# led.net
KiCad netlist of a schematic drawn in EAGLE
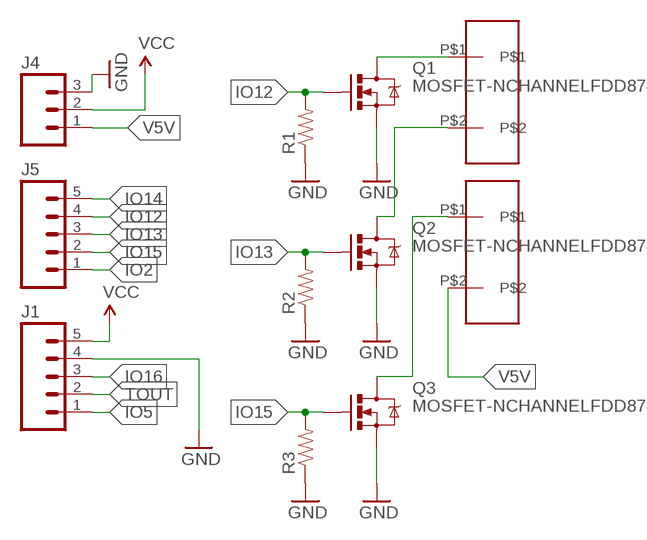
[diagram p0: schematic, sheet 1]

(export (version "E")
  (design (tool "Eeschema 10.0.6"))
  (components
    (comp (ref "J1")
      (value "M05PTH")
      (footprint "eagle-import:1X05")
      (libsource (lib "eagle-import") (part "M05PTH"))
    )
    (comp (ref "J4")
      (value "M03PTH")
      (footprint "eagle-import:1X03")
      (libsource (lib "eagle-import") (part "M03PTH"))
    )
    (comp (ref "J5")
      (value "M05PTH")
      (footprint "eagle-import:1X05")
      (libsource (lib "eagle-import") (part "M05PTH"))
    )
    (comp (ref "Q1")
      (value "MOSFET-NCHANNELFDD8780")
      (footprint "eagle-import:DPAK")
      (libsource (lib "eagle-import") (part "MOSFET-NCHANNELFDD8780"))
    )
    (comp (ref "Q2")
      (value "MOSFET-NCHANNELFDD8780")
      (footprint "eagle-import:DPAK")
      (libsource (lib "eagle-import") (part "MOSFET-NCHANNELFDD8780"))
    )
    (comp (ref "Q3")
      (value "MOSFET-NCHANNELFDD8780")
      (footprint "eagle-import:DPAK")
      (libsource (lib "eagle-import") (part "MOSFET-NCHANNELFDD8780"))
    )
    (comp (ref "R1")
      (value "RESISTOR0805-RES")
      (footprint "eagle-import:0805")
      (libsource (lib "eagle-import") (part "RESISTOR0805-RES"))
    )
    (comp (ref "R2")
      (value "RESISTOR0805-RES")
      (footprint "eagle-import:0805")
      (libsource (lib "eagle-import") (part "RESISTOR0805-RES"))
    )
    (comp (ref "R3")
      (value "RESISTOR0805-RES")
      (footprint "eagle-import:0805")
      (libsource (lib "eagle-import") (part "RESISTOR0805-RES"))
    )
    (comp (ref "U$1")
      (value "SCREWTERMINALS_5MM_2")
      (footprint "eagle-import:TERMINAL_2X")
      (libsource (lib "eagle-import") (part "SCREWTERMINALS_5MM_2"))
    )
    (comp (ref "U$2")
      (value "SCREWTERMINALS_5MM_2")
      (footprint "eagle-import:TERMINAL_2X")
      (libsource (lib "eagle-import") (part "SCREWTERMINALS_5MM_2"))
    )
  )
  (nets
    (net (code "1") (name "GND") (class "Default")
      (node (ref "J1") (pin "4") (pinfunction "4_4") (pintype "passive"))
      (node (ref "J4") (pin "3") (pinfunction "3_3") (pintype "passive"))
      (node (ref "Q1") (pin "3") (pinfunction "S_3") (pintype "passive"))
      (node (ref "Q2") (pin "3") (pinfunction "S_3") (pintype "passive"))
      (node (ref "Q3") (pin "3") (pinfunction "S_3") (pintype "passive"))
      (node (ref "R1") (pin "1") (pinfunction "1_1") (pintype "passive"))
      (node (ref "R2") (pin "1") (pinfunction "1_1") (pintype "passive"))
      (node (ref "R3") (pin "1") (pinfunction "1_1") (pintype "passive"))
    )
    (net (code "2") (name "IO2") (class "Default")
      (node (ref "J5") (pin "1") (pinfunction "1_1") (pintype "passive"))
    )
    (net (code "3") (name "IO5") (class "Default")
      (node (ref "J1") (pin "1") (pinfunction "1_1") (pintype "passive"))
    )
    (net (code "4") (name "IO12") (class "Default")
      (node (ref "J5") (pin "4") (pinfunction "4_4") (pintype "passive"))
      (node (ref "Q1") (pin "1") (pinfunction "G_1") (pintype "passive"))
      (node (ref "R1") (pin "2") (pinfunction "2_2") (pintype "passive"))
    )
    (net (code "5") (name "IO13") (class "Default")
      (node (ref "J5") (pin "3") (pinfunction "3_3") (pintype "passive"))
      (node (ref "Q2") (pin "1") (pinfunction "G_1") (pintype "passive"))
      (node (ref "R2") (pin "2") (pinfunction "2_2") (pintype "passive"))
    )
    (net (code "6") (name "IO14") (class "Default")
      (node (ref "J5") (pin "5") (pinfunction "5_5") (pintype "passive"))
    )
    (net (code "7") (name "IO15") (class "Default")
      (node (ref "J5") (pin "2") (pinfunction "2_2") (pintype "passive"))
      (node (ref "Q3") (pin "1") (pinfunction "G_1") (pintype "passive"))
      (node (ref "R3") (pin "2") (pinfunction "2_2") (pintype "passive"))
    )
    (net (code "8") (name "IO16") (class "Default")
      (node (ref "J1") (pin "3") (pinfunction "3_3") (pintype "passive"))
    )
    (net (code "9") (name "Net-(Q1-D)") (class "Default")
      (node (ref "Q1") (pin "4") (pinfunction "D_4") (pintype "passive"))
      (node (ref "U$1") (pin "P$1") (pinfunction "P$1_P$1") (pintype "bidirectional"))
    )
    (net (code "10") (name "Net-(Q2-D)") (class "Default")
      (node (ref "Q2") (pin "4") (pinfunction "D_4") (pintype "passive"))
      (node (ref "U$1") (pin "P$2") (pinfunction "P$2_P$2") (pintype "bidirectional"))
    )
    (net (code "11") (name "Net-(Q3-D)") (class "Default")
      (node (ref "Q3") (pin "4") (pinfunction "D_4") (pintype "passive"))
      (node (ref "U$2") (pin "P$1") (pinfunction "P$1_P$1") (pintype "bidirectional"))
    )
    (net (code "12") (name "TOUT") (class "Default")
      (node (ref "J1") (pin "2") (pinfunction "2_2") (pintype "passive"))
    )
    (net (code "13") (name "V5V") (class "Default")
      (node (ref "J4") (pin "1") (pinfunction "1_1") (pintype "passive"))
      (node (ref "U$2") (pin "P$2") (pinfunction "P$2_P$2") (pintype "bidirectional"))
    )
    (net (code "14") (name "VCC") (class "Default")
      (node (ref "J1") (pin "5") (pinfunction "5_5") (pintype "passive"))
      (node (ref "J4") (pin "2") (pinfunction "2_2") (pintype "passive"))
    )
  )
)
